# CitizenBoard.net
KiCad netlist of a schematic drawn in EAGLE
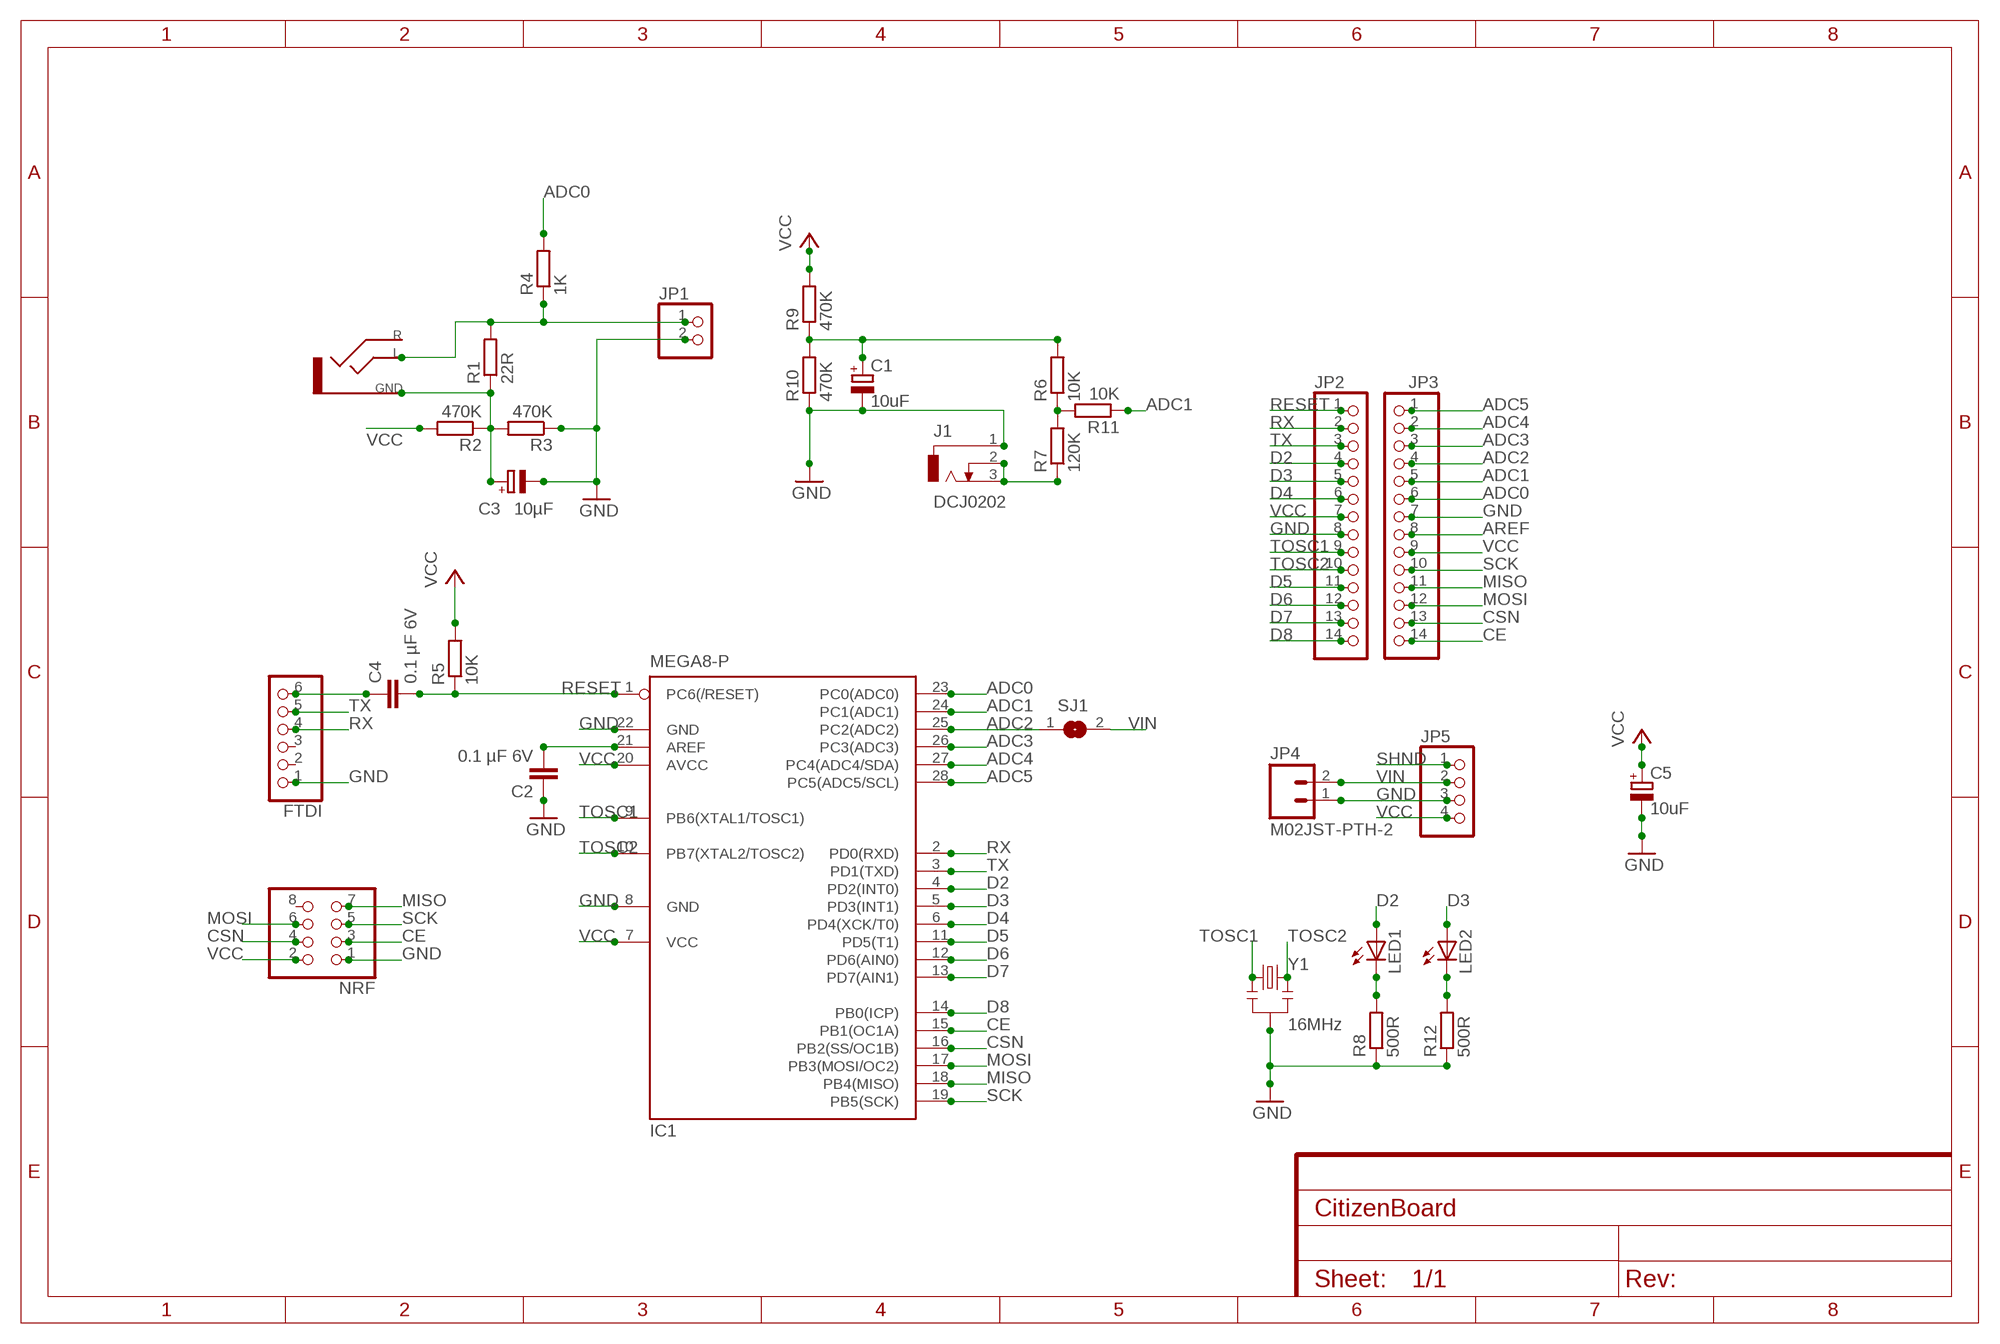
[diagram p0: schematic, sheet 1]

(export (version "E")
  (design (tool "Eeschema 10.0.6"))
  (components
    (comp (ref "C1")
      (value "10uF")
      (footprint "eagle-import:E2,5-6E")
      (libsource (lib "eagle-import") (part "CPOL-EUE2,5-6E"))
    )
    (comp (ref "C2")
      (value "0.1 µF 6V")
      (footprint "eagle-import:C025-024X044")
      (libsource (lib "eagle-import") (part "C-EU025-024X044"))
    )
    (comp (ref "C3")
      (value "10µF")
      (footprint "eagle-import:E2,5-6E")
      (libsource (lib "eagle-import") (part "CPOL-EUE2,5-6E"))
    )
    (comp (ref "C4")
      (value "0.1 µF 6V")
      (footprint "eagle-import:C025-024X044")
      (libsource (lib "eagle-import") (part "C-EU025-024X044"))
    )
    (comp (ref "C5")
      (value "10uF")
      (footprint "eagle-import:E2,5-6E")
      (libsource (lib "eagle-import") (part "CPOL-EUE2,5-6E"))
    )
    (comp (ref "FTDI")
      (value "PINHD-1X6")
      (footprint "eagle-import:1X06")
      (libsource (lib "eagle-import") (part "PINHD-1X6"))
    )
    (comp (ref "IC1")
      (value "MEGA8-P")
      (footprint "eagle-import:DIL28-3")
      (libsource (lib "eagle-import") (part "MEGA8-P"))
    )
    (comp (ref "J1")
      (value "DCJ0202")
      (footprint "eagle-import:DCJ0202")
      (libsource (lib "eagle-import") (part "DCJ0202"))
    )
    (comp (ref "J2")
      (value "AUDIO-JACK-3.5")
      (footprint "eagle-import:AUDIO-JACK-3.5")
      (libsource (lib "eagle-import") (part "AUDIO-JACK-3.5"))
    )
    (comp (ref "JP1")
      (value "PINHD-1X2")
      (footprint "eagle-import:1X02")
      (libsource (lib "eagle-import") (part "PINHD-1X2"))
    )
    (comp (ref "JP2")
      (value "PINHD-1X14")
      (footprint "eagle-import:1X14")
      (libsource (lib "eagle-import") (part "PINHD-1X14"))
    )
    (comp (ref "JP3")
      (value "PINHD-1X14")
      (footprint "eagle-import:1X14")
      (libsource (lib "eagle-import") (part "PINHD-1X14"))
    )
    (comp (ref "JP4")
      (value "M02JST-PTH-2")
      (footprint "eagle-import:JST-2-PTH")
      (libsource (lib "eagle-import") (part "M02JST-PTH-2"))
    )
    (comp (ref "JP5")
      (value "PINHD-1X4")
      (footprint "eagle-import:1X04")
      (libsource (lib "eagle-import") (part "PINHD-1X4"))
    )
    (comp (ref "LED1")
      (value "LED3MM")
      (footprint "eagle-import:LED3MM")
      (libsource (lib "eagle-import") (part "LED3MM"))
    )
    (comp (ref "LED2")
      (value "LED3MM")
      (footprint "eagle-import:LED3MM")
      (libsource (lib "eagle-import") (part "LED3MM"))
    )
    (comp (ref "NRF")
      (value "PINHD-2X4")
      (footprint "eagle-import:2X04")
      (libsource (lib "eagle-import") (part "PINHD-2X4"))
    )
    (comp (ref "R1")
      (value "22R")
      (footprint "eagle-import:0204_7")
      (libsource (lib "eagle-import") (part "R-EU_0204/7"))
    )
    (comp (ref "R2")
      (value "470K")
      (footprint "eagle-import:0204_7")
      (libsource (lib "eagle-import") (part "R-EU_0204/7"))
    )
    (comp (ref "R3")
      (value "470K")
      (footprint "eagle-import:0204_7")
      (libsource (lib "eagle-import") (part "R-EU_0204/7"))
    )
    (comp (ref "R4")
      (value "1K")
      (footprint "eagle-import:0204_7")
      (libsource (lib "eagle-import") (part "R-EU_0204/7"))
    )
    (comp (ref "R5")
      (value "10K")
      (footprint "eagle-import:0204_7")
      (libsource (lib "eagle-import") (part "R-EU_0204/7"))
    )
    (comp (ref "R6")
      (value "10K")
      (footprint "eagle-import:0204_7")
      (libsource (lib "eagle-import") (part "R-EU_0204/7"))
    )
    (comp (ref "R7")
      (value "120K")
      (footprint "eagle-import:0204_7")
      (libsource (lib "eagle-import") (part "R-EU_0204/7"))
    )
    (comp (ref "R8")
      (value "500R")
      (footprint "eagle-import:0204_7")
      (libsource (lib "eagle-import") (part "R-EU_0204/7"))
    )
    (comp (ref "R9")
      (value "470K")
      (footprint "eagle-import:0204_7")
      (libsource (lib "eagle-import") (part "R-EU_0204/7"))
    )
    (comp (ref "R10")
      (value "470K")
      (footprint "eagle-import:0204_7")
      (libsource (lib "eagle-import") (part "R-EU_0204/7"))
    )
    (comp (ref "R11")
      (value "10K")
      (footprint "eagle-import:0204_7")
      (libsource (lib "eagle-import") (part "R-EU_0204/7"))
    )
    (comp (ref "R12")
      (value "500R")
      (footprint "eagle-import:0204_7")
      (libsource (lib "eagle-import") (part "R-EU_0204/7"))
    )
    (comp (ref "SJ1") (value "SJ") (footprint "eagle-import:SJ") (libsource (lib "eagle-import") (part "SJ")))
    (comp (ref "Y1")
      (value "16MHz")
      (footprint "eagle-import:RESONATOR-PTH")
      (libsource (lib "eagle-import") (part "RESONATORPTH"))
    )
  )
  (nets
    (net (code "1") (name "/ADC0") (class "Default")
      (node (ref "IC1") (pin "23") (pinfunction "PC0(ADC0)_23") (pintype "bidirectional"))
      (node (ref "JP3") (pin "6") (pinfunction "6_6") (pintype "passive"))
      (node (ref "R4") (pin "2") (pinfunction "2_2") (pintype "passive"))
    )
    (net (code "2") (name "/ADC1") (class "Default")
      (node (ref "IC1") (pin "24") (pinfunction "PC1(ADC1)_24") (pintype "bidirectional"))
      (node (ref "JP3") (pin "5") (pinfunction "5_5") (pintype "passive"))
      (node (ref "R11") (pin "1") (pinfunction "1_1") (pintype "passive"))
    )
    (net (code "3") (name "/ADC2") (class "Default")
      (node (ref "IC1") (pin "25") (pinfunction "PC2(ADC2)_25") (pintype "bidirectional"))
      (node (ref "JP3") (pin "4") (pinfunction "4_4") (pintype "passive"))
      (node (ref "SJ1") (pin "1") (pinfunction "1_1") (pintype "passive"))
    )
    (net (code "4") (name "/ADC3") (class "Default")
      (node (ref "IC1") (pin "26") (pinfunction "PC3(ADC3)_26") (pintype "bidirectional"))
      (node (ref "JP3") (pin "3") (pinfunction "3_3") (pintype "passive"))
    )
    (net (code "5") (name "/ADC4") (class "Default")
      (node (ref "IC1") (pin "27") (pinfunction "PC4(ADC4/SDA)_27") (pintype "bidirectional"))
      (node (ref "JP3") (pin "2") (pinfunction "2_2") (pintype "passive"))
    )
    (net (code "6") (name "/ADC5") (class "Default")
      (node (ref "IC1") (pin "28") (pinfunction "PC5(ADC5/SCL)_28") (pintype "bidirectional"))
      (node (ref "JP3") (pin "1") (pinfunction "1_1") (pintype "passive"))
    )
    (net (code "7") (name "/AREF") (class "Default")
      (node (ref "C2") (pin "2") (pinfunction "2_2") (pintype "passive"))
      (node (ref "IC1") (pin "21") (pinfunction "AREF_21") (pintype "passive"))
      (node (ref "JP3") (pin "8") (pinfunction "8_8") (pintype "passive"))
    )
    (net (code "8") (name "/CE") (class "Default")
      (node (ref "IC1") (pin "15") (pinfunction "PB1(OC1A)_15") (pintype "bidirectional"))
      (node (ref "JP3") (pin "14") (pinfunction "14_14") (pintype "passive"))
      (node (ref "NRF") (pin "3") (pinfunction "3_3") (pintype "passive"))
    )
    (net (code "9") (name "/CSN") (class "Default")
      (node (ref "IC1") (pin "16") (pinfunction "PB2(SS/OC1B)_16") (pintype "bidirectional"))
      (node (ref "JP3") (pin "13") (pinfunction "13_13") (pintype "passive"))
      (node (ref "NRF") (pin "4") (pinfunction "4_4") (pintype "passive"))
    )
    (net (code "10") (name "/D2") (class "Default")
      (node (ref "IC1") (pin "4") (pinfunction "PD2(INT0)_4") (pintype "bidirectional"))
      (node (ref "JP2") (pin "4") (pinfunction "4_4") (pintype "passive"))
      (node (ref "LED1") (pin "A") (pinfunction "A_A") (pintype "passive"))
    )
    (net (code "11") (name "/D3") (class "Default")
      (node (ref "IC1") (pin "5") (pinfunction "PD3(INT1)_5") (pintype "bidirectional"))
      (node (ref "JP2") (pin "5") (pinfunction "5_5") (pintype "passive"))
      (node (ref "LED2") (pin "A") (pinfunction "A_A") (pintype "passive"))
    )
    (net (code "12") (name "/D4") (class "Default")
      (node (ref "IC1") (pin "6") (pinfunction "PD4(XCK/T0)_6") (pintype "bidirectional"))
      (node (ref "JP2") (pin "6") (pinfunction "6_6") (pintype "passive"))
    )
    (net (code "13") (name "/D5") (class "Default")
      (node (ref "IC1") (pin "11") (pinfunction "PD5(T1)_11") (pintype "bidirectional"))
      (node (ref "JP2") (pin "11") (pinfunction "11_11") (pintype "passive"))
    )
    (net (code "14") (name "/D6") (class "Default")
      (node (ref "IC1") (pin "12") (pinfunction "PD6(AIN0)_12") (pintype "bidirectional"))
      (node (ref "JP2") (pin "12") (pinfunction "12_12") (pintype "passive"))
    )
    (net (code "15") (name "/D7") (class "Default")
      (node (ref "IC1") (pin "13") (pinfunction "PD7(AIN1)_13") (pintype "bidirectional"))
      (node (ref "JP2") (pin "13") (pinfunction "13_13") (pintype "passive"))
    )
    (net (code "16") (name "/D8") (class "Default")
      (node (ref "IC1") (pin "14") (pinfunction "PB0(ICP)_14") (pintype "bidirectional"))
      (node (ref "JP2") (pin "14") (pinfunction "14_14") (pintype "passive"))
    )
    (net (code "17") (name "/MISO") (class "Default")
      (node (ref "IC1") (pin "18") (pinfunction "PB4(MISO)_18") (pintype "bidirectional"))
      (node (ref "JP3") (pin "11") (pinfunction "11_11") (pintype "passive"))
      (node (ref "NRF") (pin "7") (pinfunction "7_7") (pintype "passive"))
    )
    (net (code "18") (name "/MOSI") (class "Default")
      (node (ref "IC1") (pin "17") (pinfunction "PB3(MOSI/OC2)_17") (pintype "bidirectional"))
      (node (ref "JP3") (pin "12") (pinfunction "12_12") (pintype "passive"))
      (node (ref "NRF") (pin "6") (pinfunction "6_6") (pintype "passive"))
    )
    (net (code "19") (name "/RESET") (class "Default")
      (node (ref "C4") (pin "2") (pinfunction "2_2") (pintype "passive"))
      (node (ref "IC1") (pin "1") (pinfunction "PC6(/RESET)_1") (pintype "bidirectional"))
      (node (ref "JP2") (pin "1") (pinfunction "1_1") (pintype "passive"))
      (node (ref "R5") (pin "1") (pinfunction "1_1") (pintype "passive"))
    )
    (net (code "20") (name "/RX") (class "Default")
      (node (ref "FTDI") (pin "4") (pinfunction "4_4") (pintype "passive"))
      (node (ref "IC1") (pin "2") (pinfunction "PD0(RXD)_2") (pintype "bidirectional"))
      (node (ref "JP2") (pin "2") (pinfunction "2_2") (pintype "passive"))
    )
    (net (code "21") (name "/SCK") (class "Default")
      (node (ref "IC1") (pin "19") (pinfunction "PB5(SCK)_19") (pintype "bidirectional"))
      (node (ref "JP3") (pin "10") (pinfunction "10_10") (pintype "passive"))
      (node (ref "NRF") (pin "5") (pinfunction "5_5") (pintype "passive"))
    )
    (net (code "22") (name "/SHND") (class "Default")
      (node (ref "JP5") (pin "1") (pinfunction "1_1") (pintype "passive"))
    )
    (net (code "23") (name "/TOSC1") (class "Default")
      (node (ref "IC1") (pin "9") (pinfunction "PB6(XTAL1/TOSC1)_9") (pintype "bidirectional"))
      (node (ref "JP2") (pin "9") (pinfunction "9_9") (pintype "passive"))
      (node (ref "Y1") (pin "1") (pinfunction "1_1") (pintype "passive"))
    )
    (net (code "24") (name "/TOSC2") (class "Default")
      (node (ref "IC1") (pin "10") (pinfunction "PB7(XTAL2/TOSC2)_10") (pintype "bidirectional"))
      (node (ref "JP2") (pin "10") (pinfunction "10_10") (pintype "passive"))
      (node (ref "Y1") (pin "3") (pinfunction "3_3") (pintype "passive"))
    )
    (net (code "25") (name "/TX") (class "Default")
      (node (ref "FTDI") (pin "5") (pinfunction "5_5") (pintype "passive"))
      (node (ref "IC1") (pin "3") (pinfunction "PD1(TXD)_3") (pintype "bidirectional"))
      (node (ref "JP2") (pin "3") (pinfunction "3_3") (pintype "passive"))
    )
    (net (code "26") (name "/VIN") (class "Default")
      (node (ref "JP4") (pin "2") (pinfunction "2_2") (pintype "passive"))
      (node (ref "JP5") (pin "2") (pinfunction "2_2") (pintype "passive"))
      (node (ref "SJ1") (pin "2") (pinfunction "2_2") (pintype "passive"))
    )
    (net (code "27") (name "GND") (class "Default")
      (node (ref "C1") (pin "-") (pinfunction "-_-") (pintype "passive"))
      (node (ref "C2") (pin "1") (pinfunction "1_1") (pintype "passive"))
      (node (ref "C3") (pin "-") (pinfunction "-_-") (pintype "passive"))
      (node (ref "C5") (pin "-") (pinfunction "-_-") (pintype "passive"))
      (node (ref "FTDI") (pin "1") (pinfunction "1_1") (pintype "passive"))
      (node (ref "IC1") (pin "22") (pinfunction "GND_22") (pintype "power_in"))
      (node (ref "IC1") (pin "8") (pinfunction "GND_8") (pintype "power_in"))
      (node (ref "J1") (pin "1") (pinfunction "1_1") (pintype "passive"))
      (node (ref "JP1") (pin "2") (pinfunction "2_2") (pintype "passive"))
      (node (ref "JP2") (pin "8") (pinfunction "8_8") (pintype "passive"))
      (node (ref "JP3") (pin "7") (pinfunction "7_7") (pintype "passive"))
      (node (ref "JP4") (pin "1") (pinfunction "1_1") (pintype "passive"))
      (node (ref "JP5") (pin "3") (pinfunction "3_3") (pintype "passive"))
      (node (ref "NRF") (pin "1") (pinfunction "1_1") (pintype "passive"))
      (node (ref "R10") (pin "1") (pinfunction "1_1") (pintype "passive"))
      (node (ref "R12") (pin "1") (pinfunction "1_1") (pintype "passive"))
      (node (ref "R3") (pin "1") (pinfunction "1_1") (pintype "passive"))
      (node (ref "R8") (pin "1") (pinfunction "1_1") (pintype "passive"))
      (node (ref "Y1") (pin "2") (pinfunction "2_2") (pintype "passive"))
    )
    (net (code "28") (name "Net-(C1-Pad+)") (class "Default")
      (node (ref "C1") (pin "+") (pinfunction "+_+") (pintype "passive"))
      (node (ref "R10") (pin "2") (pinfunction "2_2") (pintype "passive"))
      (node (ref "R6") (pin "2") (pinfunction "2_2") (pintype "passive"))
      (node (ref "R9") (pin "1") (pinfunction "1_1") (pintype "passive"))
    )
    (net (code "29") (name "Net-(C4-Pad1)") (class "Default")
      (node (ref "C4") (pin "1") (pinfunction "1_1") (pintype "passive"))
      (node (ref "FTDI") (pin "6") (pinfunction "6_6") (pintype "passive"))
    )
    (net (code "30") (name "Net-(J1-Pad2)") (class "Default")
      (node (ref "J1") (pin "2") (pinfunction "2_2") (pintype "passive"))
      (node (ref "J1") (pin "3") (pinfunction "3_3") (pintype "passive"))
      (node (ref "R7") (pin "1") (pinfunction "1_1") (pintype "passive"))
    )
    (net (code "31") (name "Net-(J2-GND)") (class "Default")
      (node (ref "C3") (pin "+") (pinfunction "+_+") (pintype "passive"))
      (node (ref "J2") (pin "1S") (pinfunction "GND_1S") (pintype "bidirectional"))
      (node (ref "R1") (pin "1") (pinfunction "1_1") (pintype "passive"))
      (node (ref "R2") (pin "1") (pinfunction "1_1") (pintype "passive"))
      (node (ref "R3") (pin "2") (pinfunction "2_2") (pintype "passive"))
    )
    (net (code "32") (name "Net-(J2-L)") (class "Default")
      (node (ref "J2") (pin "5T") (pinfunction "L_5T") (pintype "bidirectional"))
      (node (ref "JP1") (pin "1") (pinfunction "1_1") (pintype "passive"))
      (node (ref "R1") (pin "2") (pinfunction "2_2") (pintype "passive"))
      (node (ref "R4") (pin "1") (pinfunction "1_1") (pintype "passive"))
    )
    (net (code "33") (name "Net-(LED1-C)") (class "Default")
      (node (ref "LED1") (pin "K") (pinfunction "C_K") (pintype "passive"))
      (node (ref "R8") (pin "2") (pinfunction "2_2") (pintype "passive"))
    )
    (net (code "34") (name "Net-(LED2-C)") (class "Default")
      (node (ref "LED2") (pin "K") (pinfunction "C_K") (pintype "passive"))
      (node (ref "R12") (pin "2") (pinfunction "2_2") (pintype "passive"))
    )
    (net (code "35") (name "Net-(R11-Pad2)") (class "Default")
      (node (ref "R11") (pin "2") (pinfunction "2_2") (pintype "passive"))
      (node (ref "R6") (pin "1") (pinfunction "1_1") (pintype "passive"))
      (node (ref "R7") (pin "2") (pinfunction "2_2") (pintype "passive"))
    )
    (net (code "36") (name "VCC") (class "Default")
      (node (ref "C5") (pin "+") (pinfunction "+_+") (pintype "passive"))
      (node (ref "IC1") (pin "20") (pinfunction "AVCC_20") (pintype "power_in"))
      (node (ref "IC1") (pin "7") (pinfunction "VCC_7") (pintype "power_in"))
      (node (ref "JP2") (pin "7") (pinfunction "7_7") (pintype "passive"))
      (node (ref "JP3") (pin "9") (pinfunction "9_9") (pintype "passive"))
      (node (ref "JP5") (pin "4") (pinfunction "4_4") (pintype "passive"))
      (node (ref "NRF") (pin "2") (pinfunction "2_2") (pintype "passive"))
      (node (ref "R2") (pin "2") (pinfunction "2_2") (pintype "passive"))
      (node (ref "R5") (pin "2") (pinfunction "2_2") (pintype "passive"))
      (node (ref "R9") (pin "2") (pinfunction "2_2") (pintype "passive"))
    )
    (net (code "37") (name "unconnected-(FTDI-Pad2)") (class "Default")
      (node (ref "FTDI") (pin "2") (pinfunction "2_2") (pintype "passive"))
    )
    (net (code "38") (name "unconnected-(FTDI-Pad3)") (class "Default")
      (node (ref "FTDI") (pin "3") (pinfunction "3_3") (pintype "passive"))
    )
    (net (code "39") (name "unconnected-(J2-R-Pad2R)") (class "Default")
      (node (ref "J2") (pin "2R") (pinfunction "R_2R") (pintype "bidirectional"))
    )
    (net (code "40") (name "unconnected-(NRF-Pad8)") (class "Default")
      (node (ref "NRF") (pin "8") (pinfunction "8_8") (pintype "passive"))
    )
  )
)
